# connector_boards.net
KiCad netlist of a schematic drawn in EAGLE
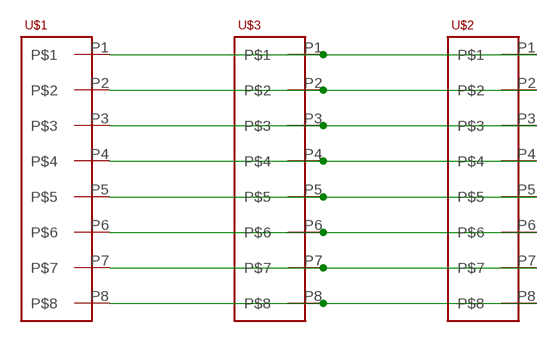
[diagram p0: schematic, sheet 1]

(export (version "E")
  (design (tool "Eeschema 10.0.6"))
  (components
    (comp (ref "U$1")
      (value "8-PIN-MOLEX-RA-FEMALE")
      (footprint "eagle-import:8-PIN-MOLEX")
      (libsource (lib "eagle-import") (part "8-PIN-MOLEX-RA-FEMALE"))
    )
    (comp (ref "U$2")
      (value "8-PIN-MOLEX-RA-FEMALE")
      (footprint "eagle-import:8-PIN-MOLEX")
      (libsource (lib "eagle-import") (part "8-PIN-MOLEX-RA-FEMALE"))
    )
    (comp (ref "U$3")
      (value "8-PIN-MOLEX-RA-FEMALE")
      (footprint "eagle-import:8-PIN-MOLEX")
      (libsource (lib "eagle-import") (part "8-PIN-MOLEX-RA-FEMALE"))
    )
  )
  (nets
    (net (code "1") (name "Net-(U$1-P$1)") (class "Default")
      (node (ref "U$1") (pin "P1") (pinfunction "P$1_P1") (pintype "bidirectional"))
      (node (ref "U$2") (pin "P1") (pinfunction "P$1_P1") (pintype "bidirectional"))
      (node (ref "U$3") (pin "P1") (pinfunction "P$1_P1") (pintype "bidirectional"))
    )
    (net (code "2") (name "Net-(U$1-P$2)") (class "Default")
      (node (ref "U$1") (pin "P2") (pinfunction "P$2_P2") (pintype "bidirectional"))
      (node (ref "U$2") (pin "P2") (pinfunction "P$2_P2") (pintype "bidirectional"))
      (node (ref "U$3") (pin "P2") (pinfunction "P$2_P2") (pintype "bidirectional"))
    )
    (net (code "3") (name "Net-(U$1-P$3)") (class "Default")
      (node (ref "U$1") (pin "P3") (pinfunction "P$3_P3") (pintype "bidirectional"))
      (node (ref "U$2") (pin "P3") (pinfunction "P$3_P3") (pintype "bidirectional"))
      (node (ref "U$3") (pin "P3") (pinfunction "P$3_P3") (pintype "bidirectional"))
    )
    (net (code "4") (name "Net-(U$1-P$4)") (class "Default")
      (node (ref "U$1") (pin "P4") (pinfunction "P$4_P4") (pintype "bidirectional"))
      (node (ref "U$2") (pin "P4") (pinfunction "P$4_P4") (pintype "bidirectional"))
      (node (ref "U$3") (pin "P4") (pinfunction "P$4_P4") (pintype "bidirectional"))
    )
    (net (code "5") (name "Net-(U$1-P$5)") (class "Default")
      (node (ref "U$1") (pin "P5") (pinfunction "P$5_P5") (pintype "bidirectional"))
      (node (ref "U$2") (pin "P5") (pinfunction "P$5_P5") (pintype "bidirectional"))
      (node (ref "U$3") (pin "P5") (pinfunction "P$5_P5") (pintype "bidirectional"))
    )
    (net (code "6") (name "Net-(U$1-P$6)") (class "Default")
      (node (ref "U$1") (pin "P6") (pinfunction "P$6_P6") (pintype "bidirectional"))
      (node (ref "U$2") (pin "P6") (pinfunction "P$6_P6") (pintype "bidirectional"))
      (node (ref "U$3") (pin "P6") (pinfunction "P$6_P6") (pintype "bidirectional"))
    )
    (net (code "7") (name "Net-(U$1-P$7)") (class "Default")
      (node (ref "U$1") (pin "P7") (pinfunction "P$7_P7") (pintype "bidirectional"))
      (node (ref "U$2") (pin "P7") (pinfunction "P$7_P7") (pintype "bidirectional"))
      (node (ref "U$3") (pin "P7") (pinfunction "P$7_P7") (pintype "bidirectional"))
    )
    (net (code "8") (name "Net-(U$1-P$8)") (class "Default")
      (node (ref "U$1") (pin "P8") (pinfunction "P$8_P8") (pintype "bidirectional"))
      (node (ref "U$2") (pin "P8") (pinfunction "P$8_P8") (pintype "bidirectional"))
      (node (ref "U$3") (pin "P8") (pinfunction "P$8_P8") (pintype "bidirectional"))
    )
  )
)
